# 07_-_USB_HUB.net
KiCad netlist of a schematic drawn in Altium Designer
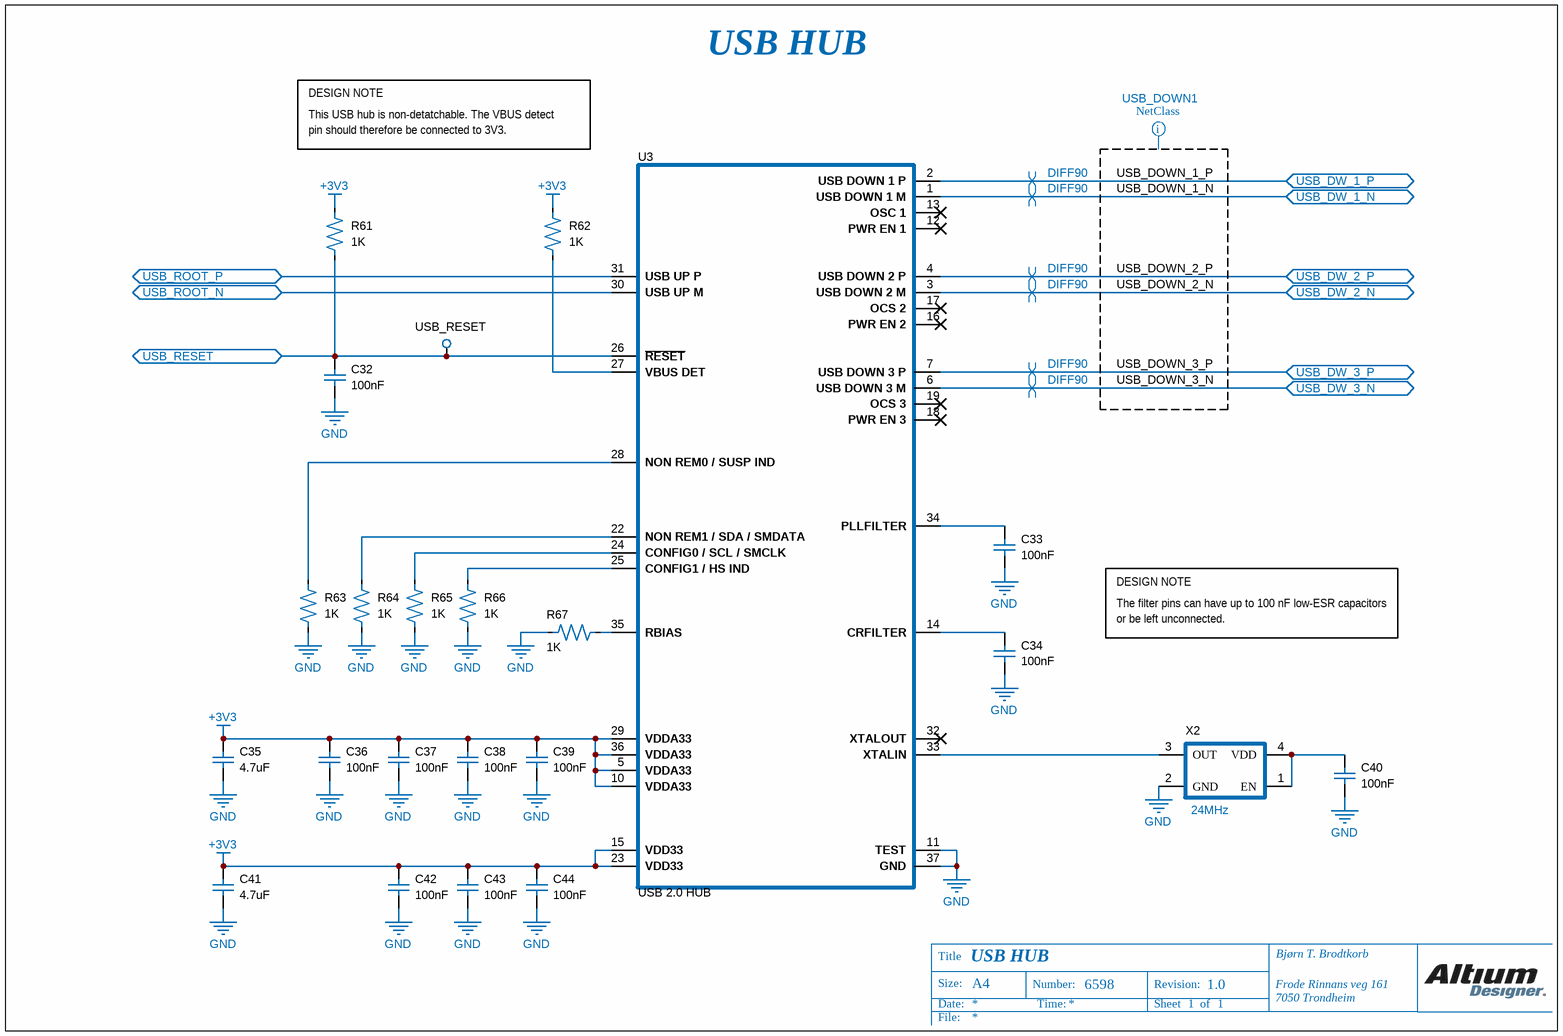
[diagram p0: [07] - USB HUB.SchDoc]

(export (version "E")
  (design (tool "Eeschema 10.0.6"))
  (components
    (comp (ref "C32")
      (value "100nF")
      (footprint "C0402")
      (description "C0402")
      (fields (field (name "Comment") "04023C103KAT2A"))
      (libsource (lib "Passive components") (part "04023C103KAT2A"))
    )
    (comp (ref "C33")
      (value "100nF")
      (footprint "C0402")
      (description "C0402")
      (fields (field (name "Comment") "04023C103KAT2A"))
      (libsource (lib "Passive components") (part "04023C103KAT2A"))
    )
    (comp (ref "C34")
      (value "100nF")
      (footprint "C0402")
      (description "C0402")
      (fields (field (name "Comment") "04023C103KAT2A"))
      (libsource (lib "Passive components") (part "04023C103KAT2A"))
    )
    (comp (ref "C35")
      (value "4.7uF")
      (footprint "C0603")
      (description "C0603")
      (fields (field (name "Comment") "02016D104KAT2A"))
      (libsource (lib "Passive components") (part "02016D104KAT2A"))
    )
    (comp (ref "C36")
      (value "100nF")
      (footprint "C0402")
      (description "C0402")
      (fields (field (name "Comment") "04023C103KAT2A"))
      (libsource (lib "Passive components") (part "04023C103KAT2A"))
    )
    (comp (ref "C37")
      (value "100nF")
      (footprint "C0402")
      (description "C0402")
      (fields (field (name "Comment") "04023C103KAT2A"))
      (libsource (lib "Passive components") (part "04023C103KAT2A"))
    )
    (comp (ref "C38")
      (value "100nF")
      (footprint "C0402")
      (description "C0402")
      (fields (field (name "Comment") "04023C103KAT2A"))
      (libsource (lib "Passive components") (part "04023C103KAT2A"))
    )
    (comp (ref "C39")
      (value "100nF")
      (footprint "C0402")
      (description "C0402")
      (fields (field (name "Comment") "04023C103KAT2A"))
      (libsource (lib "Passive components") (part "04023C103KAT2A"))
    )
    (comp (ref "C40")
      (value "100nF")
      (footprint "C0402")
      (description "C0402")
      (fields (field (name "Comment") "04023C103KAT2A"))
      (libsource (lib "Passive components") (part "04023C103KAT2A"))
    )
    (comp (ref "C41")
      (value "4.7uF")
      (footprint "C0603")
      (description "C0603")
      (fields (field (name "Comment") "02016D104KAT2A"))
      (libsource (lib "Passive components") (part "02016D104KAT2A"))
    )
    (comp (ref "C42")
      (value "100nF")
      (footprint "C0402")
      (description "C0402")
      (fields (field (name "Comment") "04023C103KAT2A"))
      (libsource (lib "Passive components") (part "04023C103KAT2A"))
    )
    (comp (ref "C43")
      (value "100nF")
      (footprint "C0402")
      (description "C0402")
      (fields (field (name "Comment") "04023C103KAT2A"))
      (libsource (lib "Passive components") (part "04023C103KAT2A"))
    )
    (comp (ref "C44")
      (value "100nF")
      (footprint "C0402")
      (description "C0402")
      (fields (field (name "Comment") "04023C103KAT2A"))
      (libsource (lib "Passive components") (part "04023C103KAT2A"))
    )
    (comp (ref "R61")
      (value "1K")
      (footprint "R0402")
      (description "R0402")
      (fields (field (name "Comment") "CRCW04020000Z0ED"))
      (libsource (lib "Passive components") (part "CRCW04020000Z0ED"))
    )
    (comp (ref "R62")
      (value "1K")
      (footprint "R0402")
      (description "R0402")
      (fields (field (name "Comment") "CRCW04020000Z0ED"))
      (libsource (lib "Passive components") (part "CRCW04020000Z0ED"))
    )
    (comp (ref "R63")
      (value "1K")
      (footprint "R0402")
      (description "R0402")
      (fields (field (name "Comment") "CRCW04020000Z0ED"))
      (libsource (lib "Passive components") (part "CRCW04020000Z0ED"))
    )
    (comp (ref "R64")
      (value "1K")
      (footprint "R0402")
      (description "R0402")
      (fields (field (name "Comment") "CRCW04020000Z0ED"))
      (libsource (lib "Passive components") (part "CRCW04020000Z0ED"))
    )
    (comp (ref "R65")
      (value "1K")
      (footprint "R0402")
      (description "R0402")
      (fields (field (name "Comment") "CRCW04020000Z0ED"))
      (libsource (lib "Passive components") (part "CRCW04020000Z0ED"))
    )
    (comp (ref "R66")
      (value "1K")
      (footprint "R0402")
      (description "R0402")
      (fields (field (name "Comment") "CRCW04020000Z0ED"))
      (libsource (lib "Passive components") (part "CRCW04020000Z0ED"))
    )
    (comp (ref "R67")
      (value "1K")
      (footprint "R0402")
      (description "R0402")
      (fields (field (name "Comment") "CRCW04020000Z0ED"))
      (libsource (lib "Passive components") (part "CRCW04020000Z0ED"))
    )
    (comp (ref "TP3")
      (value "Test point")
      (footprint "TEST POINT")
      (fields (field (name "TYPE") "USB_RESET"))
      (libsource (lib "Miscellaneous") (part "Test point"))
    )
    (comp (ref "U3")
      (value "USB 2.0 HUB")
      (footprint "USB2512B-I/M2")
      (description "USB 2.0 Hub 3x ports")
      (libsource (lib "IC") (part "USB2513B-I/M2"))
    )
    (comp (ref "X2")
      (value "24MHz")
      (footprint "MCSJK-7U-12.00-12-30-80-B-30")
      (description "Oscillator 3.2mm x 2.5mm")
      (fields (field (name "Comment") "X1G0041710031 SG-210STF 24 MHZ L"))
      (libsource (lib "Crystals") (part "X1G0041710031 SG-210STF 24 MHZ L"))
    )
  )
  (nets
    (net (code "1") (name "+3V3") (class "Default")
      (node (ref "C35") (pin "1") (pinfunction "1_1") (pintype "passive"))
      (node (ref "C36") (pin "2") (pinfunction "2_2") (pintype "passive"))
      (node (ref "C37") (pin "2") (pinfunction "2_2") (pintype "passive"))
      (node (ref "C38") (pin "2") (pinfunction "2_2") (pintype "passive"))
      (node (ref "C39") (pin "2") (pinfunction "2_2") (pintype "passive"))
      (node (ref "C41") (pin "1") (pinfunction "1_1") (pintype "passive"))
      (node (ref "C42") (pin "2") (pinfunction "2_2") (pintype "passive"))
      (node (ref "C43") (pin "2") (pinfunction "2_2") (pintype "passive"))
      (node (ref "C44") (pin "2") (pinfunction "2_2") (pintype "passive"))
      (node (ref "R61") (pin "2") (pinfunction "3_2") (pintype "passive"))
      (node (ref "R62") (pin "2") (pinfunction "3_2") (pintype "passive"))
      (node (ref "U3") (pin "10") (pinfunction "VDDA33_10") (pintype "passive"))
      (node (ref "U3") (pin "15") (pinfunction "VDD33_15") (pintype "passive"))
      (node (ref "U3") (pin "23") (pinfunction "VDD33_23") (pintype "passive"))
      (node (ref "U3") (pin "29") (pinfunction "VDDA33_29") (pintype "passive"))
      (node (ref "U3") (pin "36") (pinfunction "VDDA33_36") (pintype "passive"))
      (node (ref "U3") (pin "5") (pinfunction "VDDA33_5") (pintype "passive"))
    )
    (net (code "2") (name "/USB_DOWN_1_N") (class "Default")
      (node (ref "U3") (pin "1") (pinfunction "USB_DOWN_1_M_1") (pintype "passive"))
    )
    (net (code "3") (name "/USB_DOWN_1_P") (class "Default")
      (node (ref "U3") (pin "2") (pinfunction "USB_DOWN_1_P_2") (pintype "passive"))
    )
    (net (code "4") (name "/USB_DOWN_2_N") (class "Default")
      (node (ref "U3") (pin "3") (pinfunction "USB_DOWN_2_M_3") (pintype "passive"))
    )
    (net (code "5") (name "/USB_DOWN_2_P") (class "Default")
      (node (ref "U3") (pin "4") (pinfunction "USB_DOWN_2_P_4") (pintype "passive"))
    )
    (net (code "6") (name "/USB_DOWN_3_N") (class "Default")
      (node (ref "U3") (pin "6") (pinfunction "USB_DOWN_3_M_6") (pintype "passive"))
    )
    (net (code "7") (name "/USB_DOWN_3_P") (class "Default")
      (node (ref "U3") (pin "7") (pinfunction "USB_DOWN_3_P_7") (pintype "passive"))
    )
    (net (code "8") (name "/USB_RESET") (class "Default")
      (node (ref "C32") (pin "2") (pinfunction "2_2") (pintype "passive"))
      (node (ref "R61") (pin "1") (pinfunction "1_1") (pintype "passive"))
      (node (ref "TP3") (pin "1") (pinfunction "33_1") (pintype "passive"))
      (node (ref "U3") (pin "26") (pinfunction "~{RESET}_26") (pintype "passive"))
    )
    (net (code "9") (name "/USB_ROOT_N") (class "Default")
      (node (ref "U3") (pin "30") (pinfunction "USB_UP_M_30") (pintype "passive"))
    )
    (net (code "10") (name "/USB_ROOT_P") (class "Default")
      (node (ref "U3") (pin "31") (pinfunction "USB_UP_P_31") (pintype "passive"))
    )
    (net (code "11") (name "GND") (class "Default")
      (node (ref "C32") (pin "1") (pinfunction "1_1") (pintype "passive"))
      (node (ref "C33") (pin "1") (pinfunction "1_1") (pintype "passive"))
      (node (ref "C34") (pin "1") (pinfunction "1_1") (pintype "passive"))
      (node (ref "C35") (pin "2") (pinfunction "2_2") (pintype "passive"))
      (node (ref "C36") (pin "1") (pinfunction "1_1") (pintype "passive"))
      (node (ref "C37") (pin "1") (pinfunction "1_1") (pintype "passive"))
      (node (ref "C38") (pin "1") (pinfunction "1_1") (pintype "passive"))
      (node (ref "C39") (pin "1") (pinfunction "1_1") (pintype "passive"))
      (node (ref "C40") (pin "1") (pinfunction "1_1") (pintype "passive"))
      (node (ref "C41") (pin "2") (pinfunction "2_2") (pintype "passive"))
      (node (ref "C42") (pin "1") (pinfunction "1_1") (pintype "passive"))
      (node (ref "C43") (pin "1") (pinfunction "1_1") (pintype "passive"))
      (node (ref "C44") (pin "1") (pinfunction "1_1") (pintype "passive"))
      (node (ref "R63") (pin "1") (pinfunction "1_1") (pintype "passive"))
      (node (ref "R64") (pin "1") (pinfunction "1_1") (pintype "passive"))
      (node (ref "R65") (pin "1") (pinfunction "1_1") (pintype "passive"))
      (node (ref "R66") (pin "1") (pinfunction "1_1") (pintype "passive"))
      (node (ref "R67") (pin "1") (pinfunction "1_1") (pintype "passive"))
      (node (ref "U3") (pin "11") (pinfunction "TEST_11") (pintype "passive"))
      (node (ref "U3") (pin "37") (pinfunction "GND_37") (pintype "passive"))
      (node (ref "X2") (pin "2") (pinfunction "GND_2") (pintype "passive"))
    )
    (net (code "12") (name "Net-(R63-3)") (class "Default")
      (node (ref "R63") (pin "2") (pinfunction "3_2") (pintype "passive"))
      (node (ref "U3") (pin "28") (pinfunction "NON_REM0_/_SUSP_IND_28") (pintype "passive"))
    )
    (net (code "13") (name "Net-(R64-3)") (class "Default")
      (node (ref "R64") (pin "2") (pinfunction "3_2") (pintype "passive"))
      (node (ref "U3") (pin "22") (pinfunction "NON_REM1_/_SDA_/_SMDATA_22") (pintype "passive"))
    )
    (net (code "14") (name "Net-(R65-3)") (class "Default")
      (node (ref "R65") (pin "2") (pinfunction "3_2") (pintype "passive"))
      (node (ref "U3") (pin "24") (pinfunction "CONFIG0_/_SCL_/_SMCLK_24") (pintype "passive"))
    )
    (net (code "15") (name "Net-(R66-3)") (class "Default")
      (node (ref "R66") (pin "2") (pinfunction "3_2") (pintype "passive"))
      (node (ref "U3") (pin "25") (pinfunction "CONFIG1_/_HS_IND_25") (pintype "passive"))
    )
    (net (code "16") (name "Net-(R67-3)") (class "Default")
      (node (ref "R67") (pin "2") (pinfunction "3_2") (pintype "passive"))
      (node (ref "U3") (pin "35") (pinfunction "RBIAS_35") (pintype "passive"))
    )
    (net (code "17") (name "Net-(U3-CRFILTER)") (class "Default")
      (node (ref "C34") (pin "2") (pinfunction "2_2") (pintype "passive"))
      (node (ref "U3") (pin "14") (pinfunction "CRFILTER_14") (pintype "passive"))
    )
    (net (code "18") (name "Net-(U3-PLLFILTER)") (class "Default")
      (node (ref "C33") (pin "2") (pinfunction "2_2") (pintype "passive"))
      (node (ref "U3") (pin "34") (pinfunction "PLLFILTER_34") (pintype "passive"))
    )
    (net (code "19") (name "Net-(U3-VBUS_DET)") (class "Default")
      (node (ref "R62") (pin "1") (pinfunction "1_1") (pintype "passive"))
      (node (ref "U3") (pin "27") (pinfunction "VBUS_DET_27") (pintype "passive"))
    )
    (net (code "20") (name "Net-(U3-XTALIN)") (class "Default")
      (node (ref "U3") (pin "33") (pinfunction "XTALIN_33") (pintype "passive"))
      (node (ref "X2") (pin "3") (pinfunction "OUT_3") (pintype "passive"))
    )
    (net (code "21") (name "Net-(X2-EN)") (class "Default")
      (node (ref "C40") (pin "2") (pinfunction "2_2") (pintype "passive"))
      (node (ref "X2") (pin "1") (pinfunction "EN_1") (pintype "passive"))
      (node (ref "X2") (pin "4") (pinfunction "VDD_4") (pintype "passive"))
    )
    (net (code "22") (name "unconnected-(U3-OCS_2-Pad17)") (class "Default")
      (node (ref "U3") (pin "17") (pinfunction "OCS_2_17") (pintype "passive+no_connect"))
    )
    (net (code "23") (name "unconnected-(U3-OCS_3-Pad19)") (class "Default")
      (node (ref "U3") (pin "19") (pinfunction "OCS_3_19") (pintype "passive+no_connect"))
    )
    (net (code "24") (name "unconnected-(U3-OSC_1-Pad13)") (class "Default")
      (node (ref "U3") (pin "13") (pinfunction "OSC_1_13") (pintype "passive+no_connect"))
    )
    (net (code "25") (name "unconnected-(U3-PWR_EN_1-Pad12)") (class "Default")
      (node (ref "U3") (pin "12") (pinfunction "PWR_EN_1_12") (pintype "passive+no_connect"))
    )
    (net (code "26") (name "unconnected-(U3-PWR_EN_2-Pad16)") (class "Default")
      (node (ref "U3") (pin "16") (pinfunction "PWR_EN_2_16") (pintype "passive+no_connect"))
    )
    (net (code "27") (name "unconnected-(U3-PWR_EN_3-Pad18)") (class "Default")
      (node (ref "U3") (pin "18") (pinfunction "PWR_EN_3_18") (pintype "passive+no_connect"))
    )
    (net (code "28") (name "unconnected-(U3-XTALOUT-Pad32)") (class "Default")
      (node (ref "U3") (pin "32") (pinfunction "XTALOUT_32") (pintype "passive+no_connect"))
    )
  )
)
